# esc_interface.net
KiCad netlist of a schematic drawn in EAGLE
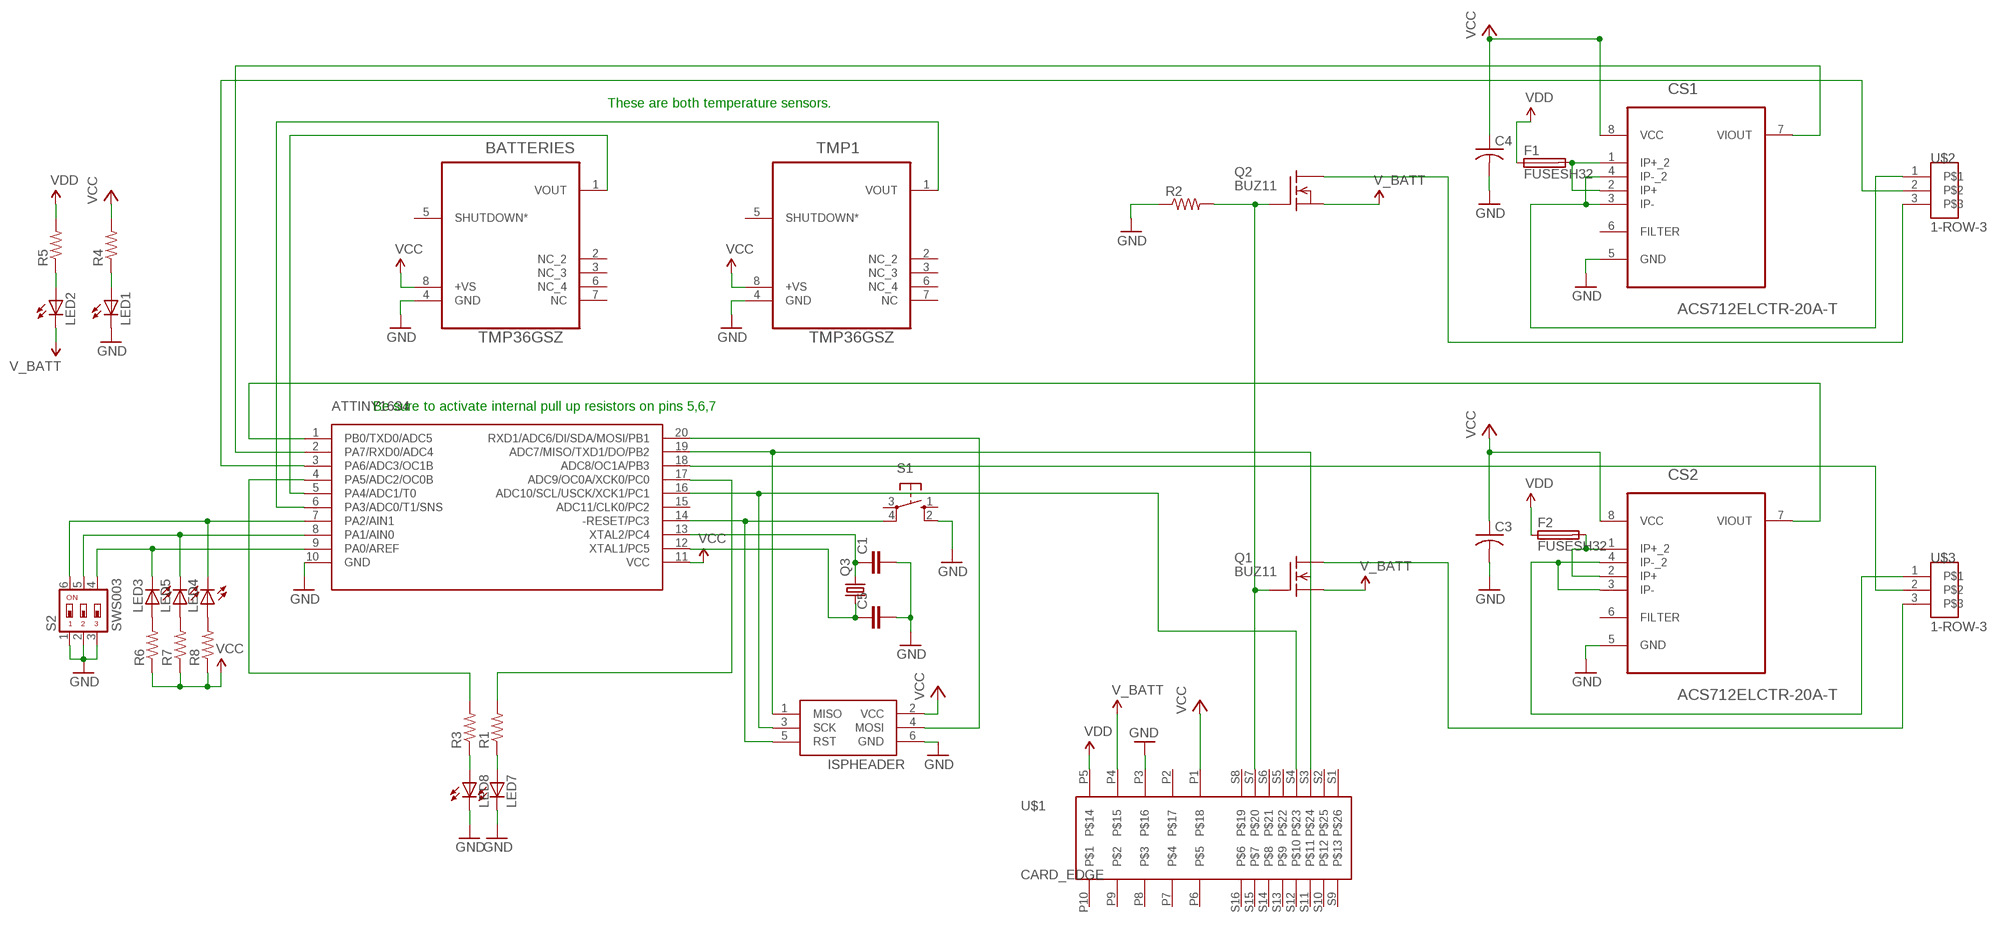
[diagram p0: schematic, sheet 1]

(export (version "E")
  (design (tool "Eeschema 10.0.6"))
  (components
    (comp (ref "ATTINY1634")
      (value "ATTINY1634SOIC20")
      (footprint "eagle-import:SOIC20")
      (libsource (lib "eagle-import") (part "ATTINY1634SOIC20"))
    )
    (comp (ref "BATTERIES")
      (value "TMP36GSZ")
      (footprint "eagle-import:SOIC127P600X175-8N")
      (libsource (lib "eagle-import") (part "TMP36GSZ"))
    )
    (comp (ref "C1")
      (value "0.1UF-50V-20%(PTH)KIT-EZ")
      (footprint "eagle-import:CAP-PTH-SMALL-KIT")
      (libsource (lib "eagle-import") (part "0.1UF-50V-20%(PTH)KIT-EZ"))
    )
    (comp (ref "C3")
      (value "C-US025-030X050")
      (footprint "eagle-import:C025-030X050")
      (libsource (lib "eagle-import") (part "C-US025-030X050"))
    )
    (comp (ref "C4")
      (value "C-US025-030X050")
      (footprint "eagle-import:C025-030X050")
      (libsource (lib "eagle-import") (part "C-US025-030X050"))
    )
    (comp (ref "C5")
      (value "0.1UF-50V-20%(PTH)KIT-EZ")
      (footprint "eagle-import:CAP-PTH-SMALL-KIT")
      (libsource (lib "eagle-import") (part "0.1UF-50V-20%(PTH)KIT-EZ"))
    )
    (comp (ref "CS1")
      (value "ACS712ELCTR-20A-T")
      (footprint "eagle-import:SOIC127P600X175-8N")
      (libsource (lib "eagle-import") (part "ACS712ELCTR-20A-T"))
    )
    (comp (ref "CS2")
      (value "ACS712ELCTR-20A-T")
      (footprint "eagle-import:SOIC127P600X175-8N")
      (libsource (lib "eagle-import") (part "ACS712ELCTR-20A-T"))
    )
    (comp (ref "F1")
      (value "FUSESH32")
      (footprint "eagle-import:SH32")
      (libsource (lib "eagle-import") (part "FUSESH32"))
    )
    (comp (ref "F2")
      (value "FUSESH32")
      (footprint "eagle-import:SH32")
      (libsource (lib "eagle-import") (part "FUSESH32"))
    )
    (comp (ref "ISPHEADER")
      (value "AVRISP-6")
      (footprint "eagle-import:AVRISP")
      (libsource (lib "eagle-import") (part "AVRISP-6"))
    )
    (comp (ref "LED1")
      (value "LEDCHIP-LED0805")
      (footprint "eagle-import:CHIP-LED0805")
      (libsource (lib "eagle-import") (part "LEDCHIP-LED0805"))
    )
    (comp (ref "LED2")
      (value "LEDCHIP-LED0805")
      (footprint "eagle-import:CHIP-LED0805")
      (libsource (lib "eagle-import") (part "LEDCHIP-LED0805"))
    )
    (comp (ref "LED3")
      (value "LEDCHIP-LED0805")
      (footprint "eagle-import:CHIP-LED0805")
      (libsource (lib "eagle-import") (part "LEDCHIP-LED0805"))
    )
    (comp (ref "LED4")
      (value "LEDCHIP-LED0805")
      (footprint "eagle-import:CHIP-LED0805")
      (libsource (lib "eagle-import") (part "LEDCHIP-LED0805"))
    )
    (comp (ref "LED5")
      (value "LEDCHIP-LED0805")
      (footprint "eagle-import:CHIP-LED0805")
      (libsource (lib "eagle-import") (part "LEDCHIP-LED0805"))
    )
    (comp (ref "LED7")
      (value "LEDCHIP-LED0805")
      (footprint "eagle-import:CHIP-LED0805")
      (libsource (lib "eagle-import") (part "LEDCHIP-LED0805"))
    )
    (comp (ref "LED8")
      (value "LEDCHIP-LED0805")
      (footprint "eagle-import:CHIP-LED0805")
      (libsource (lib "eagle-import") (part "LEDCHIP-LED0805"))
    )
    (comp (ref "Q1")
      (value "BUZ11")
      (footprint "eagle-import:TO220")
      (libsource (lib "eagle-import") (part "BUZ11"))
    )
    (comp (ref "Q2")
      (value "BUZ11")
      (footprint "eagle-import:TO220")
      (libsource (lib "eagle-import") (part "BUZ11"))
    )
    (comp (ref "Q3")
      (value "CRYSTALHC49S")
      (footprint "eagle-import:HC49_S")
      (libsource (lib "eagle-import") (part "CRYSTALHC49S"))
    )
    (comp (ref "R1")
      (value "R-US_M2012")
      (footprint "eagle-import:M2012")
      (libsource (lib "eagle-import") (part "R-US_M2012"))
    )
    (comp (ref "R2")
      (value "R-US_M2012")
      (footprint "eagle-import:M2012")
      (libsource (lib "eagle-import") (part "R-US_M2012"))
    )
    (comp (ref "R3")
      (value "R-US_M2012")
      (footprint "eagle-import:M2012")
      (libsource (lib "eagle-import") (part "R-US_M2012"))
    )
    (comp (ref "R4")
      (value "R-US_M2012")
      (footprint "eagle-import:M2012")
      (libsource (lib "eagle-import") (part "R-US_M2012"))
    )
    (comp (ref "R5")
      (value "R-US_M2012")
      (footprint "eagle-import:M2012")
      (libsource (lib "eagle-import") (part "R-US_M2012"))
    )
    (comp (ref "R6")
      (value "R-US_M2012")
      (footprint "eagle-import:M2012")
      (libsource (lib "eagle-import") (part "R-US_M2012"))
    )
    (comp (ref "R7")
      (value "R-US_M2012")
      (footprint "eagle-import:M2012")
      (libsource (lib "eagle-import") (part "R-US_M2012"))
    )
    (comp (ref "R8")
      (value "R-US_M2012")
      (footprint "eagle-import:M2012")
      (libsource (lib "eagle-import") (part "R-US_M2012"))
    )
    (comp (ref "S1")
      (value "10-XX")
      (footprint "eagle-import:B3F-10XX")
      (fields (field (name "MPN") "B3F-1000"))
      (libsource (lib "eagle-import") (part "10-XX"))
    )
    (comp (ref "S2")
      (value "SWS003")
      (footprint "eagle-import:SMS-003")
      (libsource (lib "eagle-import") (part "SWS003"))
    )
    (comp (ref "TMP1")
      (value "TMP36GSZ")
      (footprint "eagle-import:SOIC127P600X175-8N")
      (libsource (lib "eagle-import") (part "TMP36GSZ"))
    )
    (comp (ref "U$1")
      (value "CARD_EDGE")
      (footprint "eagle-import:EDGE_CONNECTOR")
      (libsource (lib "eagle-import") (part "CARD_EDGE"))
    )
    (comp (ref "U$2")
      (value "1-ROW-3")
      (footprint "eagle-import:1-ROW")
      (libsource (lib "eagle-import") (part "1-ROW-3"))
    )
    (comp (ref "U$3")
      (value "1-ROW-3")
      (footprint "eagle-import:1-ROW")
      (libsource (lib "eagle-import") (part "1-ROW-3"))
    )
  )
  (nets
    (net (code "1") (name "GND") (class "Default")
      (node (ref "ATTINY1634") (pin "10") (pinfunction "GND_10") (pintype "power_in"))
      (node (ref "BATTERIES") (pin "4") (pinfunction "GND_4") (pintype "passive"))
      (node (ref "C1") (pin "2") (pinfunction "2_2") (pintype "passive"))
      (node (ref "C3") (pin "2") (pinfunction "2_2") (pintype "passive"))
      (node (ref "C4") (pin "2") (pinfunction "2_2") (pintype "passive"))
      (node (ref "C5") (pin "2") (pinfunction "2_2") (pintype "passive"))
      (node (ref "CS1") (pin "5") (pinfunction "GND_5") (pintype "passive"))
      (node (ref "CS2") (pin "5") (pinfunction "GND_5") (pintype "passive"))
      (node (ref "ISPHEADER") (pin "6") (pinfunction "GND_6") (pintype "power_in"))
      (node (ref "LED1") (pin "C") (pinfunction "C_C") (pintype "passive"))
      (node (ref "LED7") (pin "C") (pinfunction "C_C") (pintype "passive"))
      (node (ref "LED8") (pin "C") (pinfunction "C_C") (pintype "passive"))
      (node (ref "R2") (pin "1") (pinfunction "1_1") (pintype "passive"))
      (node (ref "S1") (pin "2") (pinfunction "S1_2") (pintype "passive"))
      (node (ref "S2") (pin "1") (pinfunction "1_1") (pintype "passive"))
      (node (ref "S2") (pin "2") (pinfunction "2_2") (pintype "passive"))
      (node (ref "S2") (pin "3") (pinfunction "3_3") (pintype "passive"))
      (node (ref "TMP1") (pin "4") (pinfunction "GND_4") (pintype "passive"))
      (node (ref "U$1") (pin "P3") (pinfunction "P$16_P3") (pintype "bidirectional"))
    )
    (net (code "2") (name "Net-(ATTINY1634--RESET{slash}PC3)") (class "Default")
      (node (ref "ATTINY1634") (pin "14") (pinfunction "-RESET/PC3_14") (pintype "bidirectional"))
      (node (ref "ISPHEADER") (pin "5") (pinfunction "RST_5") (pintype "output"))
      (node (ref "S1") (pin "4") (pinfunction "P1_4") (pintype "passive"))
    )
    (net (code "3") (name "Net-(ATTINY1634-ADC7{slash}MISO{slash}TXD1{slash}DO{slash}PB2)") (class "Default")
      (node (ref "ATTINY1634") (pin "19") (pinfunction "ADC7/MISO/TXD1/DO/PB2_19") (pintype "bidirectional"))
      (node (ref "ISPHEADER") (pin "1") (pinfunction "MISO_1") (pintype "input"))
      (node (ref "U$1") (pin "S3") (pinfunction "P$24_S3") (pintype "bidirectional"))
    )
    (net (code "4") (name "Net-(ATTINY1634-ADC8{slash}OC1A{slash}PB3)") (class "Default")
      (node (ref "ATTINY1634") (pin "18") (pinfunction "ADC8/OC1A/PB3_18") (pintype "bidirectional"))
      (node (ref "U$3") (pin "2") (pinfunction "P$2_2") (pintype "bidirectional"))
    )
    (net (code "5") (name "Net-(ATTINY1634-ADC9{slash}OC0A{slash}XCK0{slash}PC0)") (class "Default")
      (node (ref "ATTINY1634") (pin "17") (pinfunction "ADC9/OC0A/XCK0/PC0_17") (pintype "bidirectional"))
      (node (ref "R1") (pin "2") (pinfunction "2_2") (pintype "passive"))
    )
    (net (code "6") (name "Net-(ATTINY1634-ADC10{slash}SCL{slash}USCK{slash}XCK1{slash}PC1)") (class "Default")
      (node (ref "ATTINY1634") (pin "16") (pinfunction "ADC10/SCL/USCK/XCK1/PC1_16") (pintype "bidirectional"))
      (node (ref "ISPHEADER") (pin "3") (pinfunction "SCK_3") (pintype "output"))
      (node (ref "U$1") (pin "S4") (pinfunction "P$23_S4") (pintype "bidirectional"))
    )
    (net (code "7") (name "Net-(ATTINY1634-PA0{slash}AREF)") (class "Default")
      (node (ref "ATTINY1634") (pin "9") (pinfunction "PA0/AREF_9") (pintype "bidirectional"))
      (node (ref "LED3") (pin "C") (pinfunction "C_C") (pintype "passive"))
      (node (ref "S2") (pin "4") (pinfunction "4_4") (pintype "passive"))
    )
    (net (code "8") (name "Net-(ATTINY1634-PA1{slash}AIN0)") (class "Default")
      (node (ref "ATTINY1634") (pin "8") (pinfunction "PA1/AIN0_8") (pintype "bidirectional"))
      (node (ref "LED5") (pin "C") (pinfunction "C_C") (pintype "passive"))
      (node (ref "S2") (pin "5") (pinfunction "5_5") (pintype "passive"))
    )
    (net (code "9") (name "Net-(ATTINY1634-PA2{slash}AIN1)") (class "Default")
      (node (ref "ATTINY1634") (pin "7") (pinfunction "PA2/AIN1_7") (pintype "bidirectional"))
      (node (ref "LED4") (pin "C") (pinfunction "C_C") (pintype "passive"))
      (node (ref "S2") (pin "6") (pinfunction "6_6") (pintype "passive"))
    )
    (net (code "10") (name "Net-(ATTINY1634-PA3{slash}ADC0{slash}T1{slash}SNS)") (class "Default")
      (node (ref "ATTINY1634") (pin "6") (pinfunction "PA3/ADC0/T1/SNS_6") (pintype "bidirectional"))
      (node (ref "TMP1") (pin "1") (pinfunction "VOUT_1") (pintype "passive"))
    )
    (net (code "11") (name "Net-(ATTINY1634-PA4{slash}ADC1{slash}T0)") (class "Default")
      (node (ref "ATTINY1634") (pin "5") (pinfunction "PA4/ADC1/T0_5") (pintype "bidirectional"))
      (node (ref "BATTERIES") (pin "1") (pinfunction "VOUT_1") (pintype "passive"))
    )
    (net (code "12") (name "Net-(ATTINY1634-PA5{slash}ADC2{slash}OC0B)") (class "Default")
      (node (ref "ATTINY1634") (pin "4") (pinfunction "PA5/ADC2/OC0B_4") (pintype "bidirectional"))
      (node (ref "R3") (pin "2") (pinfunction "2_2") (pintype "passive"))
    )
    (net (code "13") (name "Net-(ATTINY1634-PA6{slash}ADC3{slash}OC1B)") (class "Default")
      (node (ref "ATTINY1634") (pin "3") (pinfunction "PA6/ADC3/OC1B_3") (pintype "bidirectional"))
      (node (ref "U$2") (pin "2") (pinfunction "P$2_2") (pintype "bidirectional"))
    )
    (net (code "14") (name "Net-(ATTINY1634-PA7{slash}RXD0{slash}ADC4)") (class "Default")
      (node (ref "ATTINY1634") (pin "2") (pinfunction "PA7/RXD0/ADC4_2") (pintype "bidirectional"))
      (node (ref "CS1") (pin "7") (pinfunction "VIOUT_7") (pintype "output"))
    )
    (net (code "15") (name "Net-(ATTINY1634-PB0{slash}TXD0{slash}ADC5)") (class "Default")
      (node (ref "ATTINY1634") (pin "1") (pinfunction "PB0/TXD0/ADC5_1") (pintype "bidirectional"))
      (node (ref "CS2") (pin "7") (pinfunction "VIOUT_7") (pintype "output"))
    )
    (net (code "16") (name "Net-(ATTINY1634-RXD1{slash}ADC6{slash}DI{slash}SDA{slash}MOSI{slash}PB1)") (class "Default")
      (node (ref "ATTINY1634") (pin "20") (pinfunction "RXD1/ADC6/DI/SDA/MOSI/PB1_20") (pintype "bidirectional"))
      (node (ref "ISPHEADER") (pin "4") (pinfunction "MOSI_4") (pintype "output"))
    )
    (net (code "17") (name "Net-(ATTINY1634-XTAL1{slash}PC5)") (class "Default")
      (node (ref "ATTINY1634") (pin "12") (pinfunction "XTAL1/PC5_12") (pintype "bidirectional"))
      (node (ref "C5") (pin "1") (pinfunction "1_1") (pintype "passive"))
      (node (ref "Q3") (pin "1") (pinfunction "1_1") (pintype "passive"))
    )
    (net (code "18") (name "Net-(ATTINY1634-XTAL2{slash}PC4)") (class "Default")
      (node (ref "ATTINY1634") (pin "13") (pinfunction "XTAL2/PC4_13") (pintype "bidirectional"))
      (node (ref "C1") (pin "1") (pinfunction "1_1") (pintype "passive"))
      (node (ref "Q3") (pin "2") (pinfunction "2_2") (pintype "passive"))
    )
    (net (code "19") (name "Net-(CS1-IP+)") (class "Default")
      (node (ref "CS1") (pin "1") (pinfunction "IP+_2_1") (pintype "input"))
      (node (ref "CS1") (pin "2") (pinfunction "IP+_2") (pintype "input"))
      (node (ref "F1") (pin "2A") (pinfunction "2_2A") (pintype "passive"))
    )
    (net (code "20") (name "Net-(CS1-IP-)") (class "Default")
      (node (ref "CS1") (pin "3") (pinfunction "IP-_3") (pintype "input"))
      (node (ref "CS1") (pin "4") (pinfunction "IP-_2_4") (pintype "input"))
      (node (ref "U$2") (pin "1") (pinfunction "P$1_1") (pintype "bidirectional"))
    )
    (net (code "21") (name "Net-(CS2-IP+)") (class "Default")
      (node (ref "CS2") (pin "1") (pinfunction "IP+_2_1") (pintype "input"))
      (node (ref "CS2") (pin "2") (pinfunction "IP+_2") (pintype "input"))
      (node (ref "F2") (pin "2A") (pinfunction "2_2A") (pintype "passive"))
    )
    (net (code "22") (name "Net-(CS2-IP-)") (class "Default")
      (node (ref "CS2") (pin "3") (pinfunction "IP-_3") (pintype "input"))
      (node (ref "CS2") (pin "4") (pinfunction "IP-_2_4") (pintype "input"))
      (node (ref "U$3") (pin "1") (pinfunction "P$1_1") (pintype "bidirectional"))
    )
    (net (code "23") (name "Net-(LED1-PadA)") (class "Default")
      (node (ref "LED1") (pin "A") (pinfunction "A_A") (pintype "passive"))
      (node (ref "R4") (pin "1") (pinfunction "1_1") (pintype "passive"))
    )
    (net (code "24") (name "Net-(LED2-PadA)") (class "Default")
      (node (ref "LED2") (pin "A") (pinfunction "A_A") (pintype "passive"))
      (node (ref "R5") (pin "1") (pinfunction "1_1") (pintype "passive"))
    )
    (net (code "25") (name "Net-(LED3-PadA)") (class "Default")
      (node (ref "LED3") (pin "A") (pinfunction "A_A") (pintype "passive"))
      (node (ref "R6") (pin "2") (pinfunction "2_2") (pintype "passive"))
    )
    (net (code "26") (name "Net-(LED4-PadA)") (class "Default")
      (node (ref "LED4") (pin "A") (pinfunction "A_A") (pintype "passive"))
      (node (ref "R8") (pin "2") (pinfunction "2_2") (pintype "passive"))
    )
    (net (code "27") (name "Net-(LED5-PadA)") (class "Default")
      (node (ref "LED5") (pin "A") (pinfunction "A_A") (pintype "passive"))
      (node (ref "R7") (pin "2") (pinfunction "2_2") (pintype "passive"))
    )
    (net (code "28") (name "Net-(LED7-PadA)") (class "Default")
      (node (ref "LED7") (pin "A") (pinfunction "A_A") (pintype "passive"))
      (node (ref "R1") (pin "1") (pinfunction "1_1") (pintype "passive"))
    )
    (net (code "29") (name "Net-(LED8-PadA)") (class "Default")
      (node (ref "LED8") (pin "A") (pinfunction "A_A") (pintype "passive"))
      (node (ref "R3") (pin "1") (pinfunction "1_1") (pintype "passive"))
    )
    (net (code "30") (name "Net-(Q1-D)") (class "Default")
      (node (ref "Q1") (pin "2") (pinfunction "D_2") (pintype "passive"))
      (node (ref "U$3") (pin "3") (pinfunction "P$3_3") (pintype "bidirectional"))
    )
    (net (code "31") (name "Net-(Q1-G)") (class "Default")
      (node (ref "Q1") (pin "1") (pinfunction "G_1") (pintype "passive"))
      (node (ref "Q2") (pin "1") (pinfunction "G_1") (pintype "passive"))
      (node (ref "R2") (pin "2") (pinfunction "2_2") (pintype "passive"))
      (node (ref "U$1") (pin "S7") (pinfunction "P$20_S7") (pintype "bidirectional"))
    )
    (net (code "32") (name "Net-(Q2-D)") (class "Default")
      (node (ref "Q2") (pin "2") (pinfunction "D_2") (pintype "passive"))
      (node (ref "U$2") (pin "3") (pinfunction "P$3_3") (pintype "bidirectional"))
    )
    (net (code "33") (name "VCC") (class "Default")
      (node (ref "ATTINY1634") (pin "11") (pinfunction "VCC_11") (pintype "power_in"))
      (node (ref "BATTERIES") (pin "8") (pinfunction "+VS_8") (pintype "power_in"))
      (node (ref "C3") (pin "1") (pinfunction "1_1") (pintype "passive"))
      (node (ref "C4") (pin "1") (pinfunction "1_1") (pintype "passive"))
      (node (ref "CS1") (pin "8") (pinfunction "VCC_8") (pintype "power_in"))
      (node (ref "CS2") (pin "8") (pinfunction "VCC_8") (pintype "power_in"))
      (node (ref "ISPHEADER") (pin "2") (pinfunction "VCC_2") (pintype "power_in"))
      (node (ref "R4") (pin "2") (pinfunction "2_2") (pintype "passive"))
      (node (ref "R6") (pin "1") (pinfunction "1_1") (pintype "passive"))
      (node (ref "R7") (pin "1") (pinfunction "1_1") (pintype "passive"))
      (node (ref "R8") (pin "1") (pinfunction "1_1") (pintype "passive"))
      (node (ref "TMP1") (pin "8") (pinfunction "+VS_8") (pintype "power_in"))
      (node (ref "U$1") (pin "P1") (pinfunction "P$18_P1") (pintype "bidirectional"))
    )
    (net (code "34") (name "VDD") (class "Default")
      (node (ref "F1") (pin "1A") (pinfunction "1_1A") (pintype "passive"))
      (node (ref "F2") (pin "1A") (pinfunction "1_1A") (pintype "passive"))
      (node (ref "R5") (pin "2") (pinfunction "2_2") (pintype "passive"))
      (node (ref "U$1") (pin "P5") (pinfunction "P$14_P5") (pintype "bidirectional"))
    )
    (net (code "35") (name "V_BATT") (class "Default")
      (node (ref "LED2") (pin "C") (pinfunction "C_C") (pintype "passive"))
      (node (ref "Q1") (pin "3") (pinfunction "S_3") (pintype "passive"))
      (node (ref "Q2") (pin "3") (pinfunction "S_3") (pintype "passive"))
      (node (ref "U$1") (pin "P4") (pinfunction "P$15_P4") (pintype "bidirectional"))
    )
    (net (code "36") (name "unconnected-(ATTINY1634-ADC11{slash}CLK0{slash}PC2-Pad15)") (class "Default")
      (node (ref "ATTINY1634") (pin "15") (pinfunction "ADC11/CLK0/PC2_15") (pintype "bidirectional"))
    )
    (net (code "37") (name "unconnected-(BATTERIES-NC-Pad7)") (class "Default")
      (node (ref "BATTERIES") (pin "7") (pinfunction "NC_7") (pintype "passive"))
    )
    (net (code "38") (name "unconnected-(BATTERIES-NC_2-Pad2)") (class "Default")
      (node (ref "BATTERIES") (pin "2") (pinfunction "NC_2_2") (pintype "passive"))
    )
    (net (code "39") (name "unconnected-(BATTERIES-NC_3-Pad3)") (class "Default")
      (node (ref "BATTERIES") (pin "3") (pinfunction "NC_3_3") (pintype "passive"))
    )
    (net (code "40") (name "unconnected-(BATTERIES-NC_4-Pad6)") (class "Default")
      (node (ref "BATTERIES") (pin "6") (pinfunction "NC_4_6") (pintype "passive"))
    )
    (net (code "41") (name "unconnected-(BATTERIES-SHUTDOWN*-Pad5)") (class "Default")
      (node (ref "BATTERIES") (pin "5") (pinfunction "SHUTDOWN*_5") (pintype "passive"))
    )
    (net (code "42") (name "unconnected-(CS1-FILTER-Pad6)") (class "Default")
      (node (ref "CS1") (pin "6") (pinfunction "FILTER_6") (pintype "input"))
    )
    (net (code "43") (name "unconnected-(CS2-FILTER-Pad6)") (class "Default")
      (node (ref "CS2") (pin "6") (pinfunction "FILTER_6") (pintype "input"))
    )
    (net (code "44") (name "unconnected-(S1-P-Pad3)") (class "Default")
      (node (ref "S1") (pin "3") (pinfunction "P_3") (pintype "passive"))
    )
    (net (code "45") (name "unconnected-(S1-S-Pad1)") (class "Default")
      (node (ref "S1") (pin "1") (pinfunction "S_1") (pintype "passive"))
    )
    (net (code "46") (name "unconnected-(TMP1-NC-Pad7)") (class "Default")
      (node (ref "TMP1") (pin "7") (pinfunction "NC_7") (pintype "passive"))
    )
    (net (code "47") (name "unconnected-(TMP1-NC_2-Pad2)") (class "Default")
      (node (ref "TMP1") (pin "2") (pinfunction "NC_2_2") (pintype "passive"))
    )
    (net (code "48") (name "unconnected-(TMP1-NC_3-Pad3)") (class "Default")
      (node (ref "TMP1") (pin "3") (pinfunction "NC_3_3") (pintype "passive"))
    )
    (net (code "49") (name "unconnected-(TMP1-NC_4-Pad6)") (class "Default")
      (node (ref "TMP1") (pin "6") (pinfunction "NC_4_6") (pintype "passive"))
    )
    (net (code "50") (name "unconnected-(TMP1-SHUTDOWN*-Pad5)") (class "Default")
      (node (ref "TMP1") (pin "5") (pinfunction "SHUTDOWN*_5") (pintype "passive"))
    )
    (net (code "51") (name "unconnected-(U$1-P$1-PadP10)") (class "Default")
      (node (ref "U$1") (pin "P10") (pinfunction "P$1_P10") (pintype "bidirectional"))
    )
    (net (code "52") (name "unconnected-(U$1-P$2-PadP9)") (class "Default")
      (node (ref "U$1") (pin "P9") (pinfunction "P$2_P9") (pintype "bidirectional"))
    )
    (net (code "53") (name "unconnected-(U$1-P$3-PadP8)") (class "Default")
      (node (ref "U$1") (pin "P8") (pinfunction "P$3_P8") (pintype "bidirectional"))
    )
    (net (code "54") (name "unconnected-(U$1-P$4-PadP7)") (class "Default")
      (node (ref "U$1") (pin "P7") (pinfunction "P$4_P7") (pintype "bidirectional"))
    )
    (net (code "55") (name "unconnected-(U$1-P$5-PadP6)") (class "Default")
      (node (ref "U$1") (pin "P6") (pinfunction "P$5_P6") (pintype "bidirectional"))
    )
    (net (code "56") (name "unconnected-(U$1-P$6-PadS16)") (class "Default")
      (node (ref "U$1") (pin "S16") (pinfunction "P$6_S16") (pintype "bidirectional"))
    )
    (net (code "57") (name "unconnected-(U$1-P$7-PadS15)") (class "Default")
      (node (ref "U$1") (pin "S15") (pinfunction "P$7_S15") (pintype "bidirectional"))
    )
    (net (code "58") (name "unconnected-(U$1-P$8-PadS14)") (class "Default")
      (node (ref "U$1") (pin "S14") (pinfunction "P$8_S14") (pintype "bidirectional"))
    )
    (net (code "59") (name "unconnected-(U$1-P$9-PadS13)") (class "Default")
      (node (ref "U$1") (pin "S13") (pinfunction "P$9_S13") (pintype "bidirectional"))
    )
    (net (code "60") (name "unconnected-(U$1-P$10-PadS12)") (class "Default")
      (node (ref "U$1") (pin "S12") (pinfunction "P$10_S12") (pintype "bidirectional"))
    )
    (net (code "61") (name "unconnected-(U$1-P$11-PadS11)") (class "Default")
      (node (ref "U$1") (pin "S11") (pinfunction "P$11_S11") (pintype "bidirectional"))
    )
    (net (code "62") (name "unconnected-(U$1-P$12-PadS10)") (class "Default")
      (node (ref "U$1") (pin "S10") (pinfunction "P$12_S10") (pintype "bidirectional"))
    )
    (net (code "63") (name "unconnected-(U$1-P$13-PadS9)") (class "Default")
      (node (ref "U$1") (pin "S9") (pinfunction "P$13_S9") (pintype "bidirectional"))
    )
    (net (code "64") (name "unconnected-(U$1-P$17-PadP2)") (class "Default")
      (node (ref "U$1") (pin "P2") (pinfunction "P$17_P2") (pintype "bidirectional"))
    )
    (net (code "65") (name "unconnected-(U$1-P$19-PadS8)") (class "Default")
      (node (ref "U$1") (pin "S8") (pinfunction "P$19_S8") (pintype "bidirectional"))
    )
    (net (code "66") (name "unconnected-(U$1-P$21-PadS6)") (class "Default")
      (node (ref "U$1") (pin "S6") (pinfunction "P$21_S6") (pintype "bidirectional"))
    )
    (net (code "67") (name "unconnected-(U$1-P$22-PadS5)") (class "Default")
      (node (ref "U$1") (pin "S5") (pinfunction "P$22_S5") (pintype "bidirectional"))
    )
    (net (code "68") (name "unconnected-(U$1-P$25-PadS2)") (class "Default")
      (node (ref "U$1") (pin "S2") (pinfunction "P$25_S2") (pintype "bidirectional"))
    )
    (net (code "69") (name "unconnected-(U$1-P$26-PadS1)") (class "Default")
      (node (ref "U$1") (pin "S1") (pinfunction "P$26_S1") (pintype "bidirectional"))
    )
  )
)
